# PCB-IEDP.net
KiCad netlist of a schematic drawn in EasyEDA
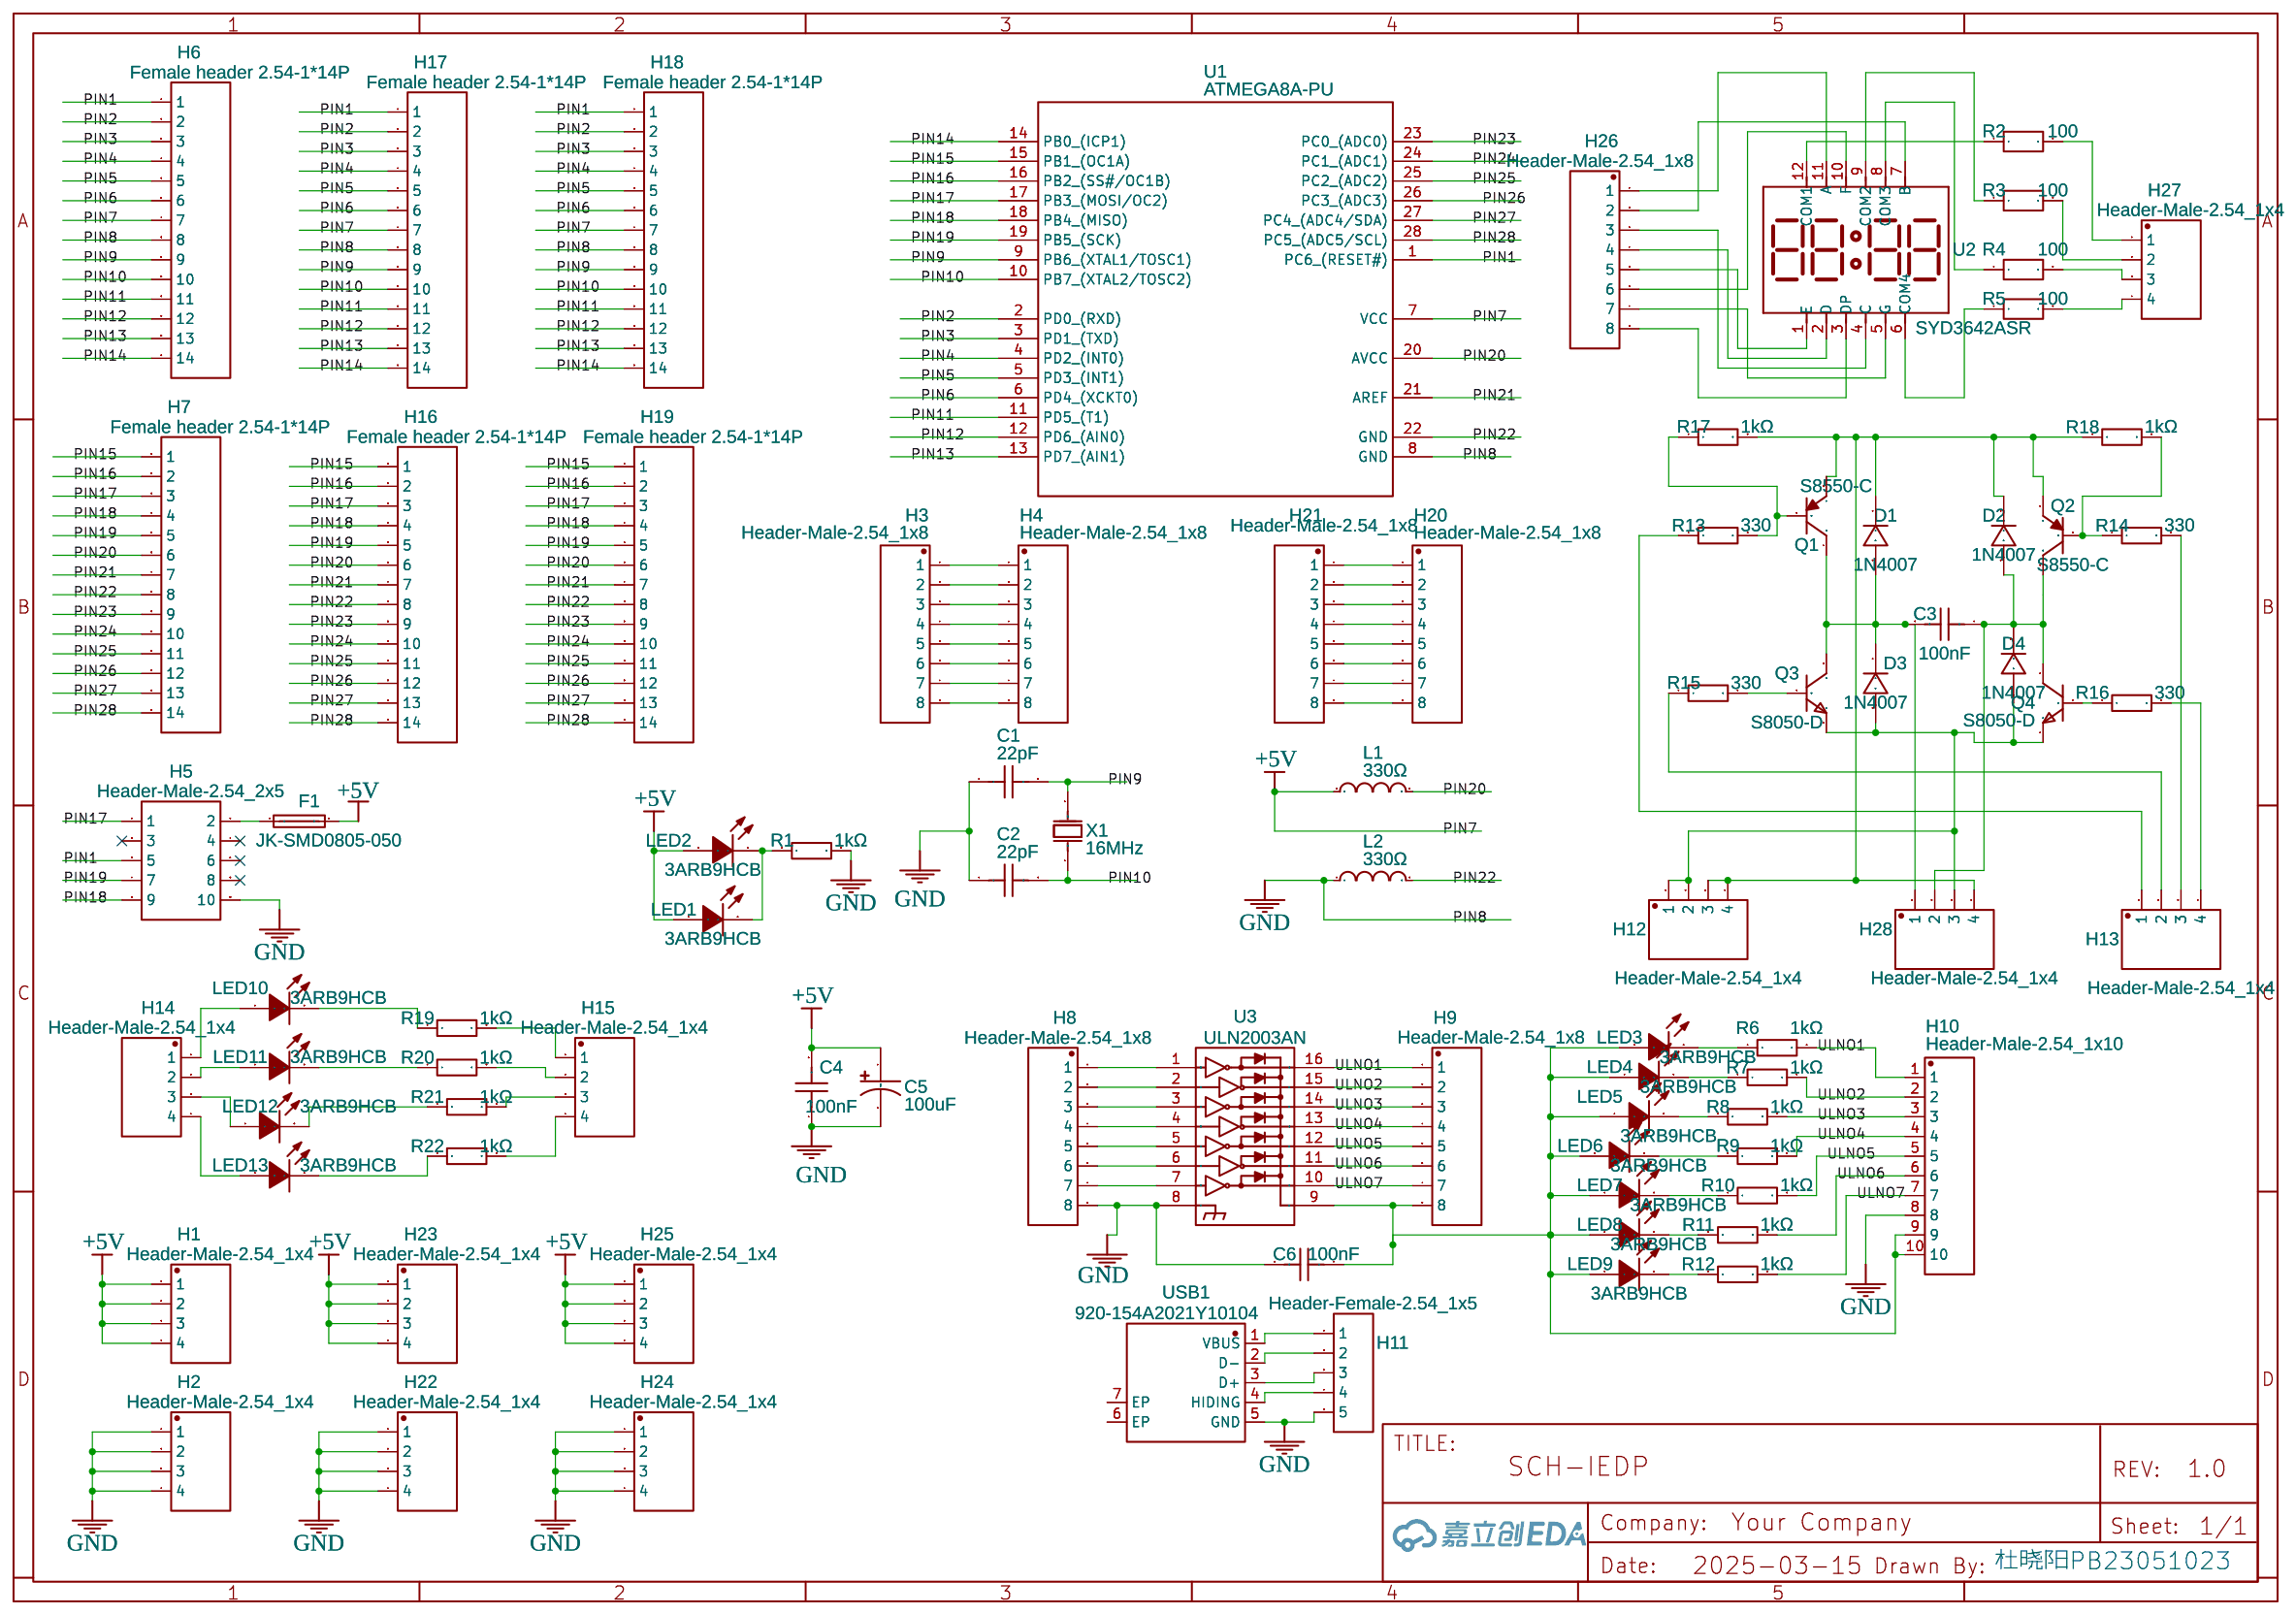
[diagram p0: schematic sheet]

(export (version "E")
  (design (tool "Eeschema 10.0.6"))
  (components
    (comp (ref "C1")
      (value "22pF")
      (fields (field (name "Manufacturer Part") "0805N220J101CT") (field (name "Manufacturer") "Walsin(华新科)"))
      (libsource (lib "") (part "0805N220J101CT"))
    )
    (comp (ref "C2")
      (value "22pF")
      (fields (field (name "Manufacturer Part") "0805N220J101CT") (field (name "Manufacturer") "Walsin(华新科)"))
      (libsource (lib "") (part "0805N220J101CT"))
    )
    (comp (ref "C3")
      (value "100nF")
      (fields (field (name "Manufacturer Part") "ACC-B104K500P52") (field (name "Manufacturer") "FH(风华)"))
      (libsource (lib "") (part "ACC-B104K500P"))
    )
    (comp (ref "C4")
      (value "100nF")
      (fields (field (name "Manufacturer Part") "ACC-B104K500P52") (field (name "Manufacturer") "FH(风华)"))
      (libsource (lib "") (part "ACC-B104K500P_1"))
    )
    (comp (ref "C5")
      (value "100uF")
      (fields
        (field (name "Manufacturer Part") "25YXA100MEFC5X11")
        (field (name "Manufacturer") "rubycon(红宝石)")
      )
      (libsource (lib "") (part "25YXA100MEFC5X11"))
    )
    (comp (ref "C6")
      (value "100nF")
      (fields (field (name "Manufacturer Part") "ACC-B104K500P52") (field (name "Manufacturer") "FH(风华)"))
      (libsource (lib "") (part "ACC-B104K500P"))
    )
    (comp (ref "D1")
      (value "1N4007")
      (fields (field (name "Manufacturer Part") "1N4007A") (field (name "Manufacturer") "LRC(乐山无线电)"))
      (libsource (lib "") (part "1N4007A"))
    )
    (comp (ref "D2")
      (value "1N4007")
      (fields (field (name "Manufacturer Part") "1N4007A") (field (name "Manufacturer") "LRC(乐山无线电)"))
      (libsource (lib "") (part "1N4007A"))
    )
    (comp (ref "D3")
      (value "1N4007")
      (fields (field (name "Manufacturer Part") "1N4007A") (field (name "Manufacturer") "LRC(乐山无线电)"))
      (libsource (lib "") (part "1N4007A"))
    )
    (comp (ref "D4")
      (value "1N4007")
      (fields (field (name "Manufacturer Part") "1N4007A") (field (name "Manufacturer") "LRC(乐山无线电)"))
      (libsource (lib "") (part "1N4007A"))
    )
    (comp (ref "F1")
      (value "JK-SMD0805-050")
      (fields (field (name "Manufacturer") "JK(金科)"))
      (libsource (lib "") (part "JK-SMD0805-050"))
    )
    (comp (ref "H1")
      (value "Header-Male-2.54_1x4")
      (fields (field (name "Manufacturer Part") "B-2100S04P-A110") (field (name "Manufacturer") "Ckmtw(灿科盟)"))
      (libsource (lib "") (part "Header-Male-2.54_1x4"))
    )
    (comp (ref "H2")
      (value "Header-Male-2.54_1x4")
      (fields (field (name "Manufacturer Part") "B-2100S04P-A110") (field (name "Manufacturer") "Ckmtw(灿科盟)"))
      (libsource (lib "") (part "Header-Male-2.54_1x4"))
    )
    (comp (ref "H3")
      (value "Header-Male-2.54_1x8")
      (fields (field (name "Manufacturer Part") "B-2100S08P-A110") (field (name "Manufacturer") "Ckmtw(灿科盟)"))
      (libsource (lib "") (part "Header-Male-2.54_1x8_1"))
    )
    (comp (ref "H4")
      (value "Header-Male-2.54_1x8")
      (fields (field (name "Manufacturer Part") "B-2100S08P-A110") (field (name "Manufacturer") "Ckmtw(灿科盟)"))
      (libsource (lib "") (part "Header-Male-2.54_1x8"))
    )
    (comp (ref "H5")
      (value "Header-Male-2.54_2x5")
      (fields (field (name "Manufacturer Part") "2*5p排针 2.54mm"))
      (libsource (lib "") (part "Header-Male-2.54_2x5"))
    )
    (comp (ref "H6")
      (value "Female header 2.54-1*14P")
      (fields (field (name "Manufacturer Part") "2.54-1*14P母") (field (name "Manufacturer") "BOOMELE(博穆精密)"))
      (libsource (lib "") (part "Female header 2.54-1*14P"))
    )
    (comp (ref "H7")
      (value "Female header 2.54-1*14P")
      (fields (field (name "Manufacturer Part") "2.54-1*14P母") (field (name "Manufacturer") "BOOMELE(博穆精密)"))
      (libsource (lib "") (part "Female header 2.54-1*14P"))
    )
    (comp (ref "H8")
      (value "Header-Male-2.54_1x8")
      (fields (field (name "Manufacturer Part") "B-2100S08P-A110") (field (name "Manufacturer") "Ckmtw(灿科盟)"))
      (libsource (lib "") (part "Header-Male-2.54_1x8_1"))
    )
    (comp (ref "H9")
      (value "Header-Male-2.54_1x8")
      (fields (field (name "Manufacturer Part") "B-2100S08P-A110") (field (name "Manufacturer") "Ckmtw(灿科盟)"))
      (libsource (lib "") (part "Header-Male-2.54_1x8"))
    )
    (comp (ref "H10")
      (value "Header-Male-2.54_1x10")
      (fields (field (name "Manufacturer Part") "2.54-1*10P针") (field (name "Manufacturer") "BOOMELE(博穆精密)"))
      (libsource (lib "") (part "Header-Male-2.54_1x10"))
    )
    (comp (ref "H11")
      (value "Header-Female-2.54_1x5")
      (fields (field (name "Manufacturer Part") "2.54-1*5P母") (field (name "Manufacturer") "BOOMELE(博穆精密)"))
      (libsource (lib "") (part "Header-Female-2.54_1x5"))
    )
    (comp (ref "H12")
      (value "Header-Male-2.54_1x4")
      (fields (field (name "Manufacturer Part") "B-2100S04P-A110") (field (name "Manufacturer") "Ckmtw(灿科盟)"))
      (libsource (lib "") (part "Header-Male-2.54_1x4_2"))
    )
    (comp (ref "H13")
      (value "Header-Male-2.54_1x4")
      (fields (field (name "Manufacturer Part") "B-2100S04P-A110") (field (name "Manufacturer") "Ckmtw(灿科盟)"))
      (libsource (lib "") (part "Header-Male-2.54_1x4_2"))
    )
    (comp (ref "H14")
      (value "Header-Male-2.54_1x4")
      (fields (field (name "Manufacturer Part") "B-2100S04P-A110") (field (name "Manufacturer") "Ckmtw(灿科盟)"))
      (libsource (lib "") (part "Header-Male-2.54_1x4_1"))
    )
    (comp (ref "H15")
      (value "Header-Male-2.54_1x4")
      (fields (field (name "Manufacturer Part") "B-2100S04P-A110") (field (name "Manufacturer") "Ckmtw(灿科盟)"))
      (libsource (lib "") (part "Header-Male-2.54_1x4"))
    )
    (comp (ref "H16")
      (value "Female header 2.54-1*14P")
      (fields (field (name "Manufacturer Part") "2.54-1*14P母") (field (name "Manufacturer") "BOOMELE(博穆精密)"))
      (libsource (lib "") (part "Female header 2.54-1*14P"))
    )
    (comp (ref "H17")
      (value "Female header 2.54-1*14P")
      (fields (field (name "Manufacturer Part") "2.54-1*14P母") (field (name "Manufacturer") "BOOMELE(博穆精密)"))
      (libsource (lib "") (part "Female header 2.54-1*14P"))
    )
    (comp (ref "H18")
      (value "Female header 2.54-1*14P")
      (fields (field (name "Manufacturer Part") "2.54-1*14P母") (field (name "Manufacturer") "BOOMELE(博穆精密)"))
      (libsource (lib "") (part "Female header 2.54-1*14P"))
    )
    (comp (ref "H19")
      (value "Female header 2.54-1*14P")
      (fields (field (name "Manufacturer Part") "2.54-1*14P母") (field (name "Manufacturer") "BOOMELE(博穆精密)"))
      (libsource (lib "") (part "Female header 2.54-1*14P"))
    )
    (comp (ref "H20")
      (value "Header-Male-2.54_1x8")
      (fields (field (name "Manufacturer Part") "B-2100S08P-A110") (field (name "Manufacturer") "Ckmtw(灿科盟)"))
      (libsource (lib "") (part "Header-Male-2.54_1x8"))
    )
    (comp (ref "H21")
      (value "Header-Male-2.54_1x8")
      (fields (field (name "Manufacturer Part") "B-2100S08P-A110") (field (name "Manufacturer") "Ckmtw(灿科盟)"))
      (libsource (lib "") (part "Header-Male-2.54_1x8_1"))
    )
    (comp (ref "H22")
      (value "Header-Male-2.54_1x4")
      (fields (field (name "Manufacturer Part") "B-2100S04P-A110") (field (name "Manufacturer") "Ckmtw(灿科盟)"))
      (libsource (lib "") (part "Header-Male-2.54_1x4"))
    )
    (comp (ref "H23")
      (value "Header-Male-2.54_1x4")
      (fields (field (name "Manufacturer Part") "B-2100S04P-A110") (field (name "Manufacturer") "Ckmtw(灿科盟)"))
      (libsource (lib "") (part "Header-Male-2.54_1x4"))
    )
    (comp (ref "H24")
      (value "Header-Male-2.54_1x4")
      (fields (field (name "Manufacturer Part") "B-2100S04P-A110") (field (name "Manufacturer") "Ckmtw(灿科盟)"))
      (libsource (lib "") (part "Header-Male-2.54_1x4"))
    )
    (comp (ref "H25")
      (value "Header-Male-2.54_1x4")
      (fields (field (name "Manufacturer Part") "B-2100S04P-A110") (field (name "Manufacturer") "Ckmtw(灿科盟)"))
      (libsource (lib "") (part "Header-Male-2.54_1x4"))
    )
    (comp (ref "H26")
      (value "Header-Male-2.54_1x8")
      (fields (field (name "Manufacturer Part") "B-2100S08P-A110") (field (name "Manufacturer") "Ckmtw(灿科盟)"))
      (libsource (lib "") (part "Header-Male-2.54_1x8_1"))
    )
    (comp (ref "H27")
      (value "Header-Male-2.54_1x4")
      (fields (field (name "Manufacturer Part") "B-2100S04P-A110") (field (name "Manufacturer") "Ckmtw(灿科盟)"))
      (libsource (lib "") (part "Header-Male-2.54_1x4"))
    )
    (comp (ref "H28")
      (value "Header-Male-2.54_1x4")
      (fields (field (name "Manufacturer Part") "B-2100S04P-A110") (field (name "Manufacturer") "Ckmtw(灿科盟)"))
      (libsource (lib "") (part "Header-Male-2.54_1x4_2"))
    )
    (comp (ref "L1")
      (value "330Ω")
      (fields (field (name "Manufacturer Part") "CBG201209U301T") (field (name "Manufacturer") "FH(风华)"))
      (libsource (lib "") (part "CBG201209U301T"))
    )
    (comp (ref "L2")
      (value "330Ω")
      (fields (field (name "Manufacturer Part") "CBG201209U301T") (field (name "Manufacturer") "FH(风华)"))
      (libsource (lib "") (part "CBG201209U301T"))
    )
    (comp (ref "LED1") (value "3ARB9HCB") (libsource (lib "") (part "3ARB9HCB")))
    (comp (ref "LED2") (value "3ARB9HCB") (libsource (lib "") (part "3ARB9HCB")))
    (comp (ref "LED3") (value "3ARB9HCB") (libsource (lib "") (part "3ARB9HCB")))
    (comp (ref "LED4") (value "3ARB9HCB") (libsource (lib "") (part "3ARB9HCB")))
    (comp (ref "LED5") (value "3ARB9HCB") (libsource (lib "") (part "3ARB9HCB")))
    (comp (ref "LED6") (value "3ARB9HCB") (libsource (lib "") (part "3ARB9HCB")))
    (comp (ref "LED7") (value "3ARB9HCB") (libsource (lib "") (part "3ARB9HCB")))
    (comp (ref "LED8") (value "3ARB9HCB") (libsource (lib "") (part "3ARB9HCB")))
    (comp (ref "LED9") (value "3ARB9HCB") (libsource (lib "") (part "3ARB9HCB")))
    (comp (ref "LED10") (value "3ARB9HCB") (libsource (lib "") (part "3ARB9HCB")))
    (comp (ref "LED11") (value "3ARB9HCB") (libsource (lib "") (part "3ARB9HCB")))
    (comp (ref "LED12") (value "3ARB9HCB") (libsource (lib "") (part "3ARB9HCB")))
    (comp (ref "LED13") (value "3ARB9HCB") (libsource (lib "") (part "3ARB9HCB")))
    (comp (ref "Q1")
      (value "S8550-C")
      (fields (field (name "Manufacturer") "BLUE ROCKET(蓝箭)"))
      (libsource (lib "") (part "S8550-C"))
    )
    (comp (ref "Q2")
      (value "S8550-C")
      (fields (field (name "Manufacturer") "BLUE ROCKET(蓝箭)"))
      (libsource (lib "") (part "S8550-C_1"))
    )
    (comp (ref "Q3")
      (value "S8050-D")
      (fields (field (name "Manufacturer") "BLUE ROCKET(蓝箭)"))
      (libsource (lib "") (part "S8050-D_1"))
    )
    (comp (ref "Q4")
      (value "S8050-D")
      (fields (field (name "Manufacturer") "BLUE ROCKET(蓝箭)"))
      (libsource (lib "") (part "S8050-D"))
    )
    (comp (ref "R1")
      (value "1kΩ")
      (fields
        (field (name "Manufacturer Part") "TR0805B1K00P0525Z")
        (field (name "Manufacturer") "EVER OHMS(天二科技)")
      )
      (libsource (lib "") (part "TR0805B1KP0525"))
    )
    (comp (ref "R2")
      (value "100")
      (fields (field (name "Manufacturer Part") "Y145313K0000V9L") (field (name "Manufacturer") "VISHAY(威世)"))
      (libsource (lib "") (part "Y145313K0000V9L"))
    )
    (comp (ref "R3")
      (value "100")
      (fields (field (name "Manufacturer Part") "Y145313K0000V9L") (field (name "Manufacturer") "VISHAY(威世)"))
      (libsource (lib "") (part "Y145313K0000V9L"))
    )
    (comp (ref "R4")
      (value "100")
      (fields (field (name "Manufacturer Part") "Y145313K0000V9L") (field (name "Manufacturer") "VISHAY(威世)"))
      (libsource (lib "") (part "Y145313K0000V9L"))
    )
    (comp (ref "R5")
      (value "100")
      (fields (field (name "Manufacturer Part") "Y145313K0000V9L") (field (name "Manufacturer") "VISHAY(威世)"))
      (libsource (lib "") (part "Y145313K0000V9L"))
    )
    (comp (ref "R6")
      (value "1kΩ")
      (fields
        (field (name "Manufacturer Part") "TR0805B1K00P0525Z")
        (field (name "Manufacturer") "EVER OHMS(天二科技)")
      )
      (libsource (lib "") (part "TR0805B1KP0525"))
    )
    (comp (ref "R7")
      (value "1kΩ")
      (fields
        (field (name "Manufacturer Part") "TR0805B1K00P0525Z")
        (field (name "Manufacturer") "EVER OHMS(天二科技)")
      )
      (libsource (lib "") (part "TR0805B1KP0525"))
    )
    (comp (ref "R8")
      (value "1kΩ")
      (fields
        (field (name "Manufacturer Part") "TR0805B1K00P0525Z")
        (field (name "Manufacturer") "EVER OHMS(天二科技)")
      )
      (libsource (lib "") (part "TR0805B1KP0525"))
    )
    (comp (ref "R9")
      (value "1kΩ")
      (fields
        (field (name "Manufacturer Part") "TR0805B1K00P0525Z")
        (field (name "Manufacturer") "EVER OHMS(天二科技)")
      )
      (libsource (lib "") (part "TR0805B1KP0525"))
    )
    (comp (ref "R10")
      (value "1kΩ")
      (fields
        (field (name "Manufacturer Part") "TR0805B1K00P0525Z")
        (field (name "Manufacturer") "EVER OHMS(天二科技)")
      )
      (libsource (lib "") (part "TR0805B1KP0525"))
    )
    (comp (ref "R11")
      (value "1kΩ")
      (fields
        (field (name "Manufacturer Part") "TR0805B1K00P0525Z")
        (field (name "Manufacturer") "EVER OHMS(天二科技)")
      )
      (libsource (lib "") (part "TR0805B1KP0525"))
    )
    (comp (ref "R12")
      (value "1kΩ")
      (fields
        (field (name "Manufacturer Part") "TR0805B1K00P0525Z")
        (field (name "Manufacturer") "EVER OHMS(天二科技)")
      )
      (libsource (lib "") (part "TR0805B1KP0525"))
    )
    (comp (ref "R13")
      (value "330")
      (fields
        (field (name "Manufacturer Part") "TR0805B1K00P0525Z")
        (field (name "Manufacturer") "EVER OHMS(天二科技)")
      )
      (libsource (lib "") (part "TR0805B1KP0525"))
    )
    (comp (ref "R14")
      (value "330")
      (fields
        (field (name "Manufacturer Part") "TR0805B1K00P0525Z")
        (field (name "Manufacturer") "EVER OHMS(天二科技)")
      )
      (libsource (lib "") (part "TR0805B1KP0525"))
    )
    (comp (ref "R15")
      (value "330")
      (fields
        (field (name "Manufacturer Part") "TR0805B1K00P0525Z")
        (field (name "Manufacturer") "EVER OHMS(天二科技)")
      )
      (libsource (lib "") (part "TR0805B1KP0525"))
    )
    (comp (ref "R16")
      (value "330")
      (fields
        (field (name "Manufacturer Part") "TR0805B1K00P0525Z")
        (field (name "Manufacturer") "EVER OHMS(天二科技)")
      )
      (libsource (lib "") (part "TR0805B1KP0525"))
    )
    (comp (ref "R17")
      (value "1kΩ")
      (fields
        (field (name "Manufacturer Part") "TR0805B1K00P0525Z")
        (field (name "Manufacturer") "EVER OHMS(天二科技)")
      )
      (libsource (lib "") (part "TR0805B1KP0525"))
    )
    (comp (ref "R18")
      (value "1kΩ")
      (fields
        (field (name "Manufacturer Part") "TR0805B1K00P0525Z")
        (field (name "Manufacturer") "EVER OHMS(天二科技)")
      )
      (libsource (lib "") (part "TR0805B1KP0525"))
    )
    (comp (ref "R19")
      (value "1kΩ")
      (fields
        (field (name "Manufacturer Part") "TR0805B1K00P0525Z")
        (field (name "Manufacturer") "EVER OHMS(天二科技)")
      )
      (libsource (lib "") (part "TR0805B1KP0525"))
    )
    (comp (ref "R20")
      (value "1kΩ")
      (fields
        (field (name "Manufacturer Part") "TR0805B1K00P0525Z")
        (field (name "Manufacturer") "EVER OHMS(天二科技)")
      )
      (libsource (lib "") (part "TR0805B1KP0525"))
    )
    (comp (ref "R21")
      (value "1kΩ")
      (fields
        (field (name "Manufacturer Part") "TR0805B1K00P0525Z")
        (field (name "Manufacturer") "EVER OHMS(天二科技)")
      )
      (libsource (lib "") (part "TR0805B1KP0525"))
    )
    (comp (ref "R22")
      (value "1kΩ")
      (fields
        (field (name "Manufacturer Part") "TR0805B1K00P0525Z")
        (field (name "Manufacturer") "EVER OHMS(天二科技)")
      )
      (libsource (lib "") (part "TR0805B1KP0525"))
    )
    (comp (ref "U1")
      (value "ATMEGA8A-PU")
      (fields (field (name "Manufacturer") "MICROCHIP(美国微芯)"))
      (libsource (lib "") (part "ATMEGA8A-PU"))
    )
    (comp (ref "U2") (value "SYD3642ASR") (libsource (lib "") (part "SYD3642ASR")))
    (comp (ref "U3")
      (value "ULN2003AN")
      (fields (field (name "Manufacturer") "TI(德州仪器)"))
      (libsource (lib "") (part "ULN2003AN"))
    )
    (comp (ref "USB1")
      (value "920-154A2021Y10104")
      (fields (field (name "Manufacturer") "精拓金"))
      (libsource (lib "") (part "920-154A2021Y10104"))
    )
    (comp (ref "X1")
      (value "16MHz")
      (fields (field (name "Manufacturer Part") "X49SD16MSD2SC") (field (name "Manufacturer") "YXC(扬兴晶振)"))
      (libsource (lib "") (part "X49SD16MSD2SC"))
    )
  )
  (nets
    (net (code "1") (name "+5V") (class "Default")
      (node (ref "C4") (pin "2") (pinfunction "2_2") (pintype "unspecified"))
      (node (ref "C5") (pin "1") (pinfunction "1_1") (pintype "unspecified"))
      (node (ref "F1") (pin "2") (pinfunction "2_2") (pintype "unspecified"))
      (node (ref "H1") (pin "1") (pinfunction "1_1") (pintype "unspecified"))
      (node (ref "H1") (pin "2") (pinfunction "2_2") (pintype "unspecified"))
      (node (ref "H1") (pin "3") (pinfunction "3_3") (pintype "unspecified"))
      (node (ref "H1") (pin "4") (pinfunction "4_4") (pintype "unspecified"))
      (node (ref "H17") (pin "7") (pinfunction "7_7") (pintype "input"))
      (node (ref "H18") (pin "7") (pinfunction "7_7") (pintype "input"))
      (node (ref "H23") (pin "1") (pinfunction "1_1") (pintype "unspecified"))
      (node (ref "H23") (pin "2") (pinfunction "2_2") (pintype "unspecified"))
      (node (ref "H23") (pin "3") (pinfunction "3_3") (pintype "unspecified"))
      (node (ref "H23") (pin "4") (pinfunction "4_4") (pintype "unspecified"))
      (node (ref "H25") (pin "1") (pinfunction "1_1") (pintype "unspecified"))
      (node (ref "H25") (pin "2") (pinfunction "2_2") (pintype "unspecified"))
      (node (ref "H25") (pin "3") (pinfunction "3_3") (pintype "unspecified"))
      (node (ref "H25") (pin "4") (pinfunction "4_4") (pintype "unspecified"))
      (node (ref "H6") (pin "7") (pinfunction "7_7") (pintype "input"))
      (node (ref "L1") (pin "1") (pinfunction "1_1") (pintype "unspecified"))
      (node (ref "LED1") (pin "1") (pinfunction "A_1") (pintype "unspecified"))
      (node (ref "LED2") (pin "1") (pinfunction "A_1") (pintype "unspecified"))
      (node (ref "U1") (pin "7") (pinfunction "VCC_7") (pintype "passive"))
    )
    (net (code "2") (name "/PIN1") (class "Default")
      (node (ref "H17") (pin "1") (pinfunction "1_1") (pintype "input"))
      (node (ref "H18") (pin "1") (pinfunction "1_1") (pintype "input"))
      (node (ref "H5") (pin "5") (pinfunction "5_5") (pintype "input"))
      (node (ref "H6") (pin "1") (pinfunction "1_1") (pintype "input"))
      (node (ref "U1") (pin "1") (pinfunction "PC6_(RESET#)_1") (pintype "bidirectional"))
    )
    (net (code "3") (name "/PIN2") (class "Default")
      (node (ref "H17") (pin "2") (pinfunction "2_2") (pintype "input"))
      (node (ref "H18") (pin "2") (pinfunction "2_2") (pintype "input"))
      (node (ref "H6") (pin "2") (pinfunction "2_2") (pintype "input"))
      (node (ref "U1") (pin "2") (pinfunction "PD0_(RXD)_2") (pintype "bidirectional"))
    )
    (net (code "4") (name "/PIN3") (class "Default")
      (node (ref "H17") (pin "3") (pinfunction "3_3") (pintype "input"))
      (node (ref "H18") (pin "3") (pinfunction "3_3") (pintype "input"))
      (node (ref "H6") (pin "3") (pinfunction "3_3") (pintype "input"))
      (node (ref "U1") (pin "3") (pinfunction "PD1_(TXD)_3") (pintype "bidirectional"))
    )
    (net (code "5") (name "/PIN4") (class "Default")
      (node (ref "H17") (pin "4") (pinfunction "4_4") (pintype "input"))
      (node (ref "H18") (pin "4") (pinfunction "4_4") (pintype "input"))
      (node (ref "H6") (pin "4") (pinfunction "4_4") (pintype "input"))
      (node (ref "U1") (pin "4") (pinfunction "PD2_(INT0)_4") (pintype "bidirectional"))
    )
    (net (code "6") (name "/PIN5") (class "Default")
      (node (ref "H17") (pin "5") (pinfunction "5_5") (pintype "input"))
      (node (ref "H18") (pin "5") (pinfunction "5_5") (pintype "input"))
      (node (ref "H6") (pin "5") (pinfunction "5_5") (pintype "input"))
      (node (ref "U1") (pin "5") (pinfunction "PD3_(INT1)_5") (pintype "bidirectional"))
    )
    (net (code "7") (name "/PIN6") (class "Default")
      (node (ref "H17") (pin "6") (pinfunction "6_6") (pintype "input"))
      (node (ref "H18") (pin "6") (pinfunction "6_6") (pintype "input"))
      (node (ref "H6") (pin "6") (pinfunction "6_6") (pintype "input"))
      (node (ref "U1") (pin "6") (pinfunction "PD4_(XCKT0)_6") (pintype "bidirectional"))
    )
    (net (code "8") (name "/PIN9") (class "Default")
      (node (ref "C1") (pin "2") (pinfunction "2_2") (pintype "unspecified"))
      (node (ref "H17") (pin "9") (pinfunction "9_9") (pintype "input"))
      (node (ref "H18") (pin "9") (pinfunction "9_9") (pintype "input"))
      (node (ref "H6") (pin "9") (pinfunction "9_9") (pintype "input"))
      (node (ref "U1") (pin "9") (pinfunction "PB6_(XTAL1/TOSC1)_9") (pintype "bidirectional"))
      (node (ref "X1") (pin "2") (pinfunction "OSC2_2") (pintype "input"))
    )
    (net (code "9") (name "/PIN10") (class "Default")
      (node (ref "C2") (pin "2") (pinfunction "2_2") (pintype "unspecified"))
      (node (ref "H17") (pin "10") (pinfunction "10_10") (pintype "input"))
      (node (ref "H18") (pin "10") (pinfunction "10_10") (pintype "input"))
      (node (ref "H6") (pin "10") (pinfunction "10_10") (pintype "input"))
      (node (ref "U1") (pin "10") (pinfunction "PB7_(XTAL2/TOSC2)_10") (pintype "bidirectional"))
      (node (ref "X1") (pin "1") (pinfunction "OSC1_1") (pintype "input"))
    )
    (net (code "10") (name "/PIN11") (class "Default")
      (node (ref "H17") (pin "11") (pinfunction "11_11") (pintype "input"))
      (node (ref "H18") (pin "11") (pinfunction "11_11") (pintype "input"))
      (node (ref "H6") (pin "11") (pinfunction "11_11") (pintype "input"))
      (node (ref "U1") (pin "11") (pinfunction "PD5_(T1)_11") (pintype "bidirectional"))
    )
    (net (code "11") (name "/PIN12") (class "Default")
      (node (ref "H17") (pin "12") (pinfunction "12_12") (pintype "input"))
      (node (ref "H18") (pin "12") (pinfunction "12_12") (pintype "input"))
      (node (ref "H6") (pin "12") (pinfunction "12_12") (pintype "input"))
      (node (ref "U1") (pin "12") (pinfunction "PD6_(AIN0)_12") (pintype "bidirectional"))
    )
    (net (code "12") (name "/PIN13") (class "Default")
      (node (ref "H17") (pin "13") (pinfunction "13_13") (pintype "input"))
      (node (ref "H18") (pin "13") (pinfunction "13_13") (pintype "input"))
      (node (ref "H6") (pin "13") (pinfunction "13_13") (pintype "input"))
      (node (ref "U1") (pin "13") (pinfunction "PD7_(AIN1)_13") (pintype "bidirectional"))
    )
    (net (code "13") (name "/PIN14") (class "Default")
      (node (ref "H17") (pin "14") (pinfunction "14_14") (pintype "input"))
      (node (ref "H18") (pin "14") (pinfunction "14_14") (pintype "input"))
      (node (ref "H6") (pin "14") (pinfunction "14_14") (pintype "input"))
      (node (ref "U1") (pin "14") (pinfunction "PB0_(ICP1)_14") (pintype "bidirectional"))
    )
    (net (code "14") (name "/PIN15") (class "Default")
      (node (ref "H16") (pin "1") (pinfunction "1_1") (pintype "input"))
      (node (ref "H19") (pin "1") (pinfunction "1_1") (pintype "input"))
      (node (ref "H7") (pin "1") (pinfunction "1_1") (pintype "input"))
      (node (ref "U1") (pin "15") (pinfunction "PB1_(OC1A)_15") (pintype "bidirectional"))
    )
    (net (code "15") (name "/PIN16") (class "Default")
      (node (ref "H16") (pin "2") (pinfunction "2_2") (pintype "input"))
      (node (ref "H19") (pin "2") (pinfunction "2_2") (pintype "input"))
      (node (ref "H7") (pin "2") (pinfunction "2_2") (pintype "input"))
      (node (ref "U1") (pin "16") (pinfunction "PB2_(SS#/OC1B)_16") (pintype "bidirectional"))
    )
    (net (code "16") (name "/PIN17") (class "Default")
      (node (ref "H16") (pin "3") (pinfunction "3_3") (pintype "input"))
      (node (ref "H19") (pin "3") (pinfunction "3_3") (pintype "input"))
      (node (ref "H5") (pin "1") (pinfunction "1_1") (pintype "input"))
      (node (ref "H7") (pin "3") (pinfunction "3_3") (pintype "input"))
      (node (ref "U1") (pin "17") (pinfunction "PB3_(MOSI/OC2)_17") (pintype "bidirectional"))
    )
    (net (code "17") (name "/PIN18") (class "Default")
      (node (ref "H16") (pin "4") (pinfunction "4_4") (pintype "input"))
      (node (ref "H19") (pin "4") (pinfunction "4_4") (pintype "input"))
      (node (ref "H5") (pin "9") (pinfunction "9_9") (pintype "input"))
      (node (ref "H7") (pin "4") (pinfunction "4_4") (pintype "input"))
      (node (ref "U1") (pin "18") (pinfunction "PB4_(MISO)_18") (pintype "bidirectional"))
    )
    (net (code "18") (name "/PIN19") (class "Default")
      (node (ref "H16") (pin "5") (pinfunction "5_5") (pintype "input"))
      (node (ref "H19") (pin "5") (pinfunction "5_5") (pintype "input"))
      (node (ref "H5") (pin "7") (pinfunction "7_7") (pintype "input"))
      (node (ref "H7") (pin "5") (pinfunction "5_5") (pintype "input"))
      (node (ref "U1") (pin "19") (pinfunction "PB5_(SCK)_19") (pintype "bidirectional"))
    )
    (net (code "19") (name "/PIN20") (class "Default")
      (node (ref "H16") (pin "6") (pinfunction "6_6") (pintype "input"))
      (node (ref "H19") (pin "6") (pinfunction "6_6") (pintype "input"))
      (node (ref "H7") (pin "6") (pinfunction "6_6") (pintype "input"))
      (node (ref "L1") (pin "2") (pinfunction "2_2") (pintype "unspecified"))
      (node (ref "U1") (pin "20") (pinfunction "AVCC_20") (pintype "passive"))
    )
    (net (code "20") (name "/PIN21") (class "Default")
      (node (ref "H16") (pin "7") (pinfunction "7_7") (pintype "input"))
      (node (ref "H19") (pin "7") (pinfunction "7_7") (pintype "input"))
      (node (ref "H7") (pin "7") (pinfunction "7_7") (pintype "input"))
      (node (ref "U1") (pin "21") (pinfunction "AREF_21") (pintype "unspecified"))
    )
    (net (code "21") (name "/PIN22") (class "Default")
      (node (ref "H16") (pin "8") (pinfunction "8_8") (pintype "input"))
      (node (ref "H19") (pin "8") (pinfunction "8_8") (pintype "input"))
      (node (ref "H7") (pin "8") (pinfunction "8_8") (pintype "input"))
      (node (ref "L2") (pin "2") (pinfunction "2_2") (pintype "unspecified"))
      (node (ref "U1") (pin "22") (pinfunction "GND_22") (pintype "passive"))
    )
    (net (code "22") (name "/PIN23") (class "Default")
      (node (ref "H16") (pin "9") (pinfunction "9_9") (pintype "input"))
      (node (ref "H19") (pin "9") (pinfunction "9_9") (pintype "input"))
      (node (ref "H7") (pin "9") (pinfunction "9_9") (pintype "input"))
      (node (ref "U1") (pin "23") (pinfunction "PC0_(ADC0)_23") (pintype "bidirectional"))
    )
    (net (code "23") (name "/PIN24") (class "Default")
      (node (ref "H16") (pin "10") (pinfunction "10_10") (pintype "input"))
      (node (ref "H19") (pin "10") (pinfunction "10_10") (pintype "input"))
      (node (ref "H7") (pin "10") (pinfunction "10_10") (pintype "input"))
      (node (ref "U1") (pin "24") (pinfunction "PC1_(ADC1)_24") (pintype "bidirectional"))
    )
    (net (code "24") (name "/PIN25") (class "Default")
      (node (ref "H16") (pin "11") (pinfunction "11_11") (pintype "input"))
      (node (ref "H19") (pin "11") (pinfunction "11_11") (pintype "input"))
      (node (ref "H7") (pin "11") (pinfunction "11_11") (pintype "input"))
      (node (ref "U1") (pin "25") (pinfunction "PC2_(ADC2)_25") (pintype "bidirectional"))
    )
    (net (code "25") (name "/PIN26") (class "Default")
      (node (ref "H16") (pin "12") (pinfunction "12_12") (pintype "input"))
      (node (ref "H19") (pin "12") (pinfunction "12_12") (pintype "input"))
      (node (ref "H7") (pin "12") (pinfunction "12_12") (pintype "input"))
      (node (ref "U1") (pin "26") (pinfunction "PC3_(ADC3)_26") (pintype "bidirectional"))
    )
    (net (code "26") (name "/PIN27") (class "Default")
      (node (ref "H16") (pin "13") (pinfunction "13_13") (pintype "input"))
      (node (ref "H19") (pin "13") (pinfunction "13_13") (pintype "input"))
      (node (ref "H7") (pin "13") (pinfunction "13_13") (pintype "input"))
      (node (ref "U1") (pin "27") (pinfunction "PC4_(ADC4/SDA)_27") (pintype "bidirectional"))
    )
    (net (code "27") (name "/PIN28") (class "Default")
      (node (ref "H16") (pin "14") (pinfunction "14_14") (pintype "input"))
      (node (ref "H19") (pin "14") (pinfunction "14_14") (pintype "input"))
      (node (ref "H7") (pin "14") (pinfunction "14_14") (pintype "input"))
      (node (ref "U1") (pin "28") (pinfunction "PC5_(ADC5/SCL)_28") (pintype "bidirectional"))
    )
    (net (code "28") (name "/ULNO1") (class "Default")
      (node (ref "H10") (pin "1") (pinfunction "1_1") (pintype "unspecified"))
      (node (ref "H9") (pin "1") (pinfunction "1_1") (pintype "unspecified"))
      (node (ref "R6") (pin "2") (pinfunction "2_2") (pintype "unspecified"))
      (node (ref "U3") (pin "16") (pinfunction "1C_16") (pintype "unspecified"))
    )
    (net (code "29") (name "/ULNO2") (class "Default")
      (node (ref "H10") (pin "2") (pinfunction "2_2") (pintype "unspecified"))
      (node (ref "H9") (pin "2") (pinfunction "2_2") (pintype "unspecified"))
      (node (ref "R7") (pin "2") (pinfunction "2_2") (pintype "unspecified"))
      (node (ref "U3") (pin "15") (pinfunction "2C_15") (pintype "unspecified"))
    )
    (net (code "30") (name "/ULNO3") (class "Default")
      (node (ref "H10") (pin "3") (pinfunction "3_3") (pintype "unspecified"))
      (node (ref "H9") (pin "3") (pinfunction "3_3") (pintype "unspecified"))
      (node (ref "R8") (pin "2") (pinfunction "2_2") (pintype "unspecified"))
      (node (ref "U3") (pin "14") (pinfunction "3C_14") (pintype "unspecified"))
    )
    (net (code "31") (name "/ULNO4") (class "Default")
      (node (ref "H10") (pin "4") (pinfunction "4_4") (pintype "unspecified"))
      (node (ref "H9") (pin "4") (pinfunction "4_4") (pintype "unspecified"))
      (node (ref "R9") (pin "2") (pinfunction "2_2") (pintype "unspecified"))
      (node (ref "U3") (pin "13") (pinfunction "4C_13") (pintype "unspecified"))
    )
    (net (code "32") (name "/ULNO5") (class "Default")
      (node (ref "H10") (pin "5") (pinfunction "5_5") (pintype "unspecified"))
      (node (ref "H9") (pin "5") (pinfunction "5_5") (pintype "unspecified"))
      (node (ref "R10") (pin "2") (pinfunction "2_2") (pintype "unspecified"))
      (node (ref "U3") (pin "12") (pinfunction "5C_12") (pintype "unspecified"))
    )
    (net (code "33") (name "/ULNO6") (class "Default")
      (node (ref "H10") (pin "6") (pinfunction "6_6") (pintype "unspecified"))
      (node (ref "H9") (pin "6") (pinfunction "6_6") (pintype "unspecified"))
      (node (ref "R11") (pin "2") (pinfunction "2_2") (pintype "unspecified"))
      (node (ref "U3") (pin "11") (pinfunction "6C_11") (pintype "unspecified"))
    )
    (net (code "34") (name "/ULNO7") (class "Default")
      (node (ref "H10") (pin "7") (pinfunction "7_7") (pintype "unspecified"))
      (node (ref "H9") (pin "7") (pinfunction "7_7") (pintype "unspecified"))
      (node (ref "R12") (pin "2") (pinfunction "2_2") (pintype "unspecified"))
      (node (ref "U3") (pin "10") (pinfunction "7C_10") (pintype "unspecified"))
    )
    (net (code "35") (name "GND") (class "Default")
      (node (ref "C1") (pin "1") (pinfunction "1_1") (pintype "unspecified"))
      (node (ref "C2") (pin "1") (pinfunction "1_1") (pintype "unspecified"))
      (node (ref "C4") (pin "1") (pinfunction "1_1") (pintype "unspecified"))
      (node (ref "C5") (pin "2") (pinfunction "2_2") (pintype "unspecified"))
      (node (ref "C6") (pin "2") (pinfunction "2_2") (pintype "unspecified"))
      (node (ref "H10") (pin "8") (pinfunction "8_8") (pintype "unspecified"))
      (node (ref "H11") (pin "5") (pinfunction "5_5") (pintype "input"))
      (node (ref "H17") (pin "8") (pinfunction "8_8") (pintype "input"))
      (node (ref "H18") (pin "8") (pinfunction "8_8") (pintype "input"))
      (node (ref "H2") (pin "1") (pinfunction "1_1") (pintype "unspecified"))
      (node (ref "H2") (pin "2") (pinfunction "2_2") (pintype "unspecified"))
      (node (ref "H2") (pin "3") (pinfunction "3_3") (pintype "unspecified"))
      (node (ref "H2") (pin "4") (pinfunction "4_4") (pintype "unspecified"))
      (node (ref "H22") (pin "1") (pinfunction "1_1") (pintype "unspecified"))
      (node (ref "H22") (pin "2") (pinfunction "2_2") (pintype "unspecified"))
      (node (ref "H22") (pin "3") (pinfunction "3_3") (pintype "unspecified"))
      (node (ref "H22") (pin "4") (pinfunction "4_4") (pintype "unspecified"))
      (node (ref "H24") (pin "1") (pinfunction "1_1") (pintype "unspecified"))
      (node (ref "H24") (pin "2") (pinfunction "2_2") (pintype "unspecified"))
      (node (ref "H24") (pin "3") (pinfunction "3_3") (pintype "unspecified"))
      (node (ref "H24") (pin "4") (pinfunction "4_4") (pintype "unspecified"))
      (node (ref "H5") (pin "10") (pinfunction "10_10") (pintype "input"))
      (node (ref "H6") (pin "8") (pinfunction "8_8") (pintype "input"))
      (node (ref "H8") (pin "8") (pinfunction "8_8") (pintype "unspecified"))
      (node (ref "L2") (pin "1") (pinfunction "1_1") (pintype "unspecified"))
      (node (ref "R1") (pin "2") (pinfunction "2_2") (pintype "unspecified"))
      (node (ref "U1") (pin "8") (pinfunction "GND_8") (pintype "passive"))
      (node (ref "U3") (pin "8") (pinfunction "E_8") (pintype "unspecified"))
      (node (ref "USB1") (pin "5") (pinfunction "GND_5") (pintype "unspecified"))
    )
    (net (code "36") (name "Net-(F1-Pad1)") (class "Default")
      (node (ref "F1") (pin "1") (pinfunction "1_1") (pintype "unspecified"))
      (node (ref "H5") (pin "2") (pinfunction "2_2") (pintype "input"))
    )
    (net (code "37") (name "Net-(H3-Pad1)") (class "Default")
      (node (ref "H3") (pin "1") (pinfunction "1_1") (pintype "unspecified"))
      (node (ref "H4") (pin "1") (pinfunction "1_1") (pintype "unspecified"))
    )
    (net (code "38") (name "Net-(H3-Pad2)") (class "Default")
      (node (ref "H3") (pin "2") (pinfunction "2_2") (pintype "unspecified"))
      (node (ref "H4") (pin "2") (pinfunction "2_2") (pintype "unspecified"))
    )
    (net (code "39") (name "Net-(H3-Pad3)") (class "Default")
      (node (ref "H3") (pin "3") (pinfunction "3_3") (pintype "unspecified"))
      (node (ref "H4") (pin "3") (pinfunction "3_3") (pintype "unspecified"))
    )
    (net (code "40") (name "Net-(H3-Pad4)") (class "Default")
      (node (ref "H3") (pin "4") (pinfunction "4_4") (pintype "unspecified"))
      (node (ref "H4") (pin "4") (pinfunction "4_4") (pintype "unspecified"))
    )
    (net (code "41") (name "Net-(H3-Pad5)") (class "Default")
      (node (ref "H3") (pin "5") (pinfunction "5_5") (pintype "unspecified"))
      (node (ref "H4") (pin "5") (pinfunction "5_5") (pintype "unspecified"))
    )
    (net (code "42") (name "Net-(H3-Pad6)") (class "Default")
      (node (ref "H3") (pin "6") (pinfunction "6_6") (pintype "unspecified"))
      (node (ref "H4") (pin "6") (pinfunction "6_6") (pintype "unspecified"))
    )
    (net (code "43") (name "Net-(H3-Pad7)") (class "Default")
      (node (ref "H3") (pin "7") (pinfunction "7_7") (pintype "unspecified"))
      (node (ref "H4") (pin "7") (pinfunction "7_7") (pintype "unspecified"))
    )
    (net (code "44") (name "Net-(H3-Pad8)") (class "Default")
      (node (ref "H3") (pin "8") (pinfunction "8_8") (pintype "unspecified"))
      (node (ref "H4") (pin "8") (pinfunction "8_8") (pintype "unspecified"))
    )
    (net (code "45") (name "Net-(H13-Pad1)") (class "Default")
      (node (ref "H13") (pin "1") (pinfunction "1_1") (pintype "unspecified"))
      (node (ref "R13") (pin "1") (pinfunction "1_1") (pintype "unspecified"))
    )
    (net (code "46") (name "Net-(H13-Pad2)") (class "Default")
      (node (ref "H13") (pin "2") (pinfunction "2_2") (pintype "unspecified"))
      (node (ref "R15") (pin "1") (pinfunction "1_1") (pintype "unspecified"))
    )
    (net (code "47") (name "Net-(H13-Pad3)") (class "Default")
      (node (ref "H13") (pin "3") (pinfunction "3_3") (pintype "unspecified"))
      (node (ref "R14") (pin "2") (pinfunction "2_2") (pintype "unspecified"))
    )
    (net (code "48") (name "Net-(H13-Pad4)") (class "Default")
      (node (ref "H13") (pin "4") (pinfunction "4_4") (pintype "unspecified"))
      (node (ref "R16") (pin "2") (pinfunction "2_2") (pintype "unspecified"))
    )
    (net (code "49") (name "Net-(H15-Pad1)") (class "Default")
      (node (ref "H15") (pin "1") (pinfunction "1_1") (pintype "unspecified"))
      (node (ref "R19") (pin "2") (pinfunction "2_2") (pintype "unspecified"))
    )
    (net (code "50") (name "Net-(H15-Pad2)") (class "Default")
      (node (ref "H15") (pin "2") (pinfunction "2_2") (pintype "unspecified"))
      (node (ref "R20") (pin "2") (pinfunction "2_2") (pintype "unspecified"))
    )
    (net (code "51") (name "Net-(H15-Pad3)") (class "Default")
      (node (ref "H15") (pin "3") (pinfunction "3_3") (pintype "unspecified"))
      (node (ref "R21") (pin "2") (pinfunction "2_2") (pintype "unspecified"))
    )
    (net (code "52") (name "Net-(H15-Pad4)") (class "Default")
      (node (ref "H15") (pin "4") (pinfunction "4_4") (pintype "unspecified"))
      (node (ref "R22") (pin "2") (pinfunction "2_2") (pintype "unspecified"))
    )
    (net (code "53") (name "Net-(H20-Pad1)") (class "Default")
      (node (ref "H20") (pin "1") (pinfunction "1_1") (pintype "unspecified"))
      (node (ref "H21") (pin "1") (pinfunction "1_1") (pintype "unspecified"))
    )
    (net (code "54") (name "Net-(H20-Pad2)") (class "Default")
      (node (ref "H20") (pin "2") (pinfunction "2_2") (pintype "unspecified"))
      (node (ref "H21") (pin "2") (pinfunction "2_2") (pintype "unspecified"))
    )
    (net (code "55") (name "Net-(H20-Pad3)") (class "Default")
      (node (ref "H20") (pin "3") (pinfunction "3_3") (pintype "unspecified"))
      (node (ref "H21") (pin "3") (pinfunction "3_3") (pintype "unspecified"))
    )
    (net (code "56") (name "Net-(H20-Pad4)") (class "Default")
      (node (ref "H20") (pin "4") (pinfunction "4_4") (pintype "unspecified"))
      (node (ref "H21") (pin "4") (pinfunction "4_4") (pintype "unspecified"))
    )
    (net (code "57") (name "Net-(H20-Pad5)") (class "Default")
      (node (ref "H20") (pin "5") (pinfunction "5_5") (pintype "unspecified"))
      (node (ref "H21") (pin "5") (pinfunction "5_5") (pintype "unspecified"))
    )
    (net (code "58") (name "Net-(H20-Pad6)") (class "Default")
      (node (ref "H20") (pin "6") (pinfunction "6_6") (pintype "unspecified"))
      (node (ref "H21") (pin "6") (pinfunction "6_6") (pintype "unspecified"))
    )
    (net (code "59") (name "Net-(H20-Pad7)") (class "Default")
      (node (ref "H20") (pin "7") (pinfunction "7_7") (pintype "unspecified"))
      (node (ref "H21") (pin "7") (pinfunction "7_7") (pintype "unspecified"))
    )
    (net (code "60") (name "Net-(H20-Pad8)") (class "Default")
      (node (ref "H20") (pin "8") (pinfunction "8_8") (pintype "unspecified"))
      (node (ref "H21") (pin "8") (pinfunction "8_8") (pintype "unspecified"))
    )
    (net (code "61") (name "Net-(H27-Pad1)") (class "Default")
      (node (ref "H27") (pin "1") (pinfunction "1_1") (pintype "unspecified"))
      (node (ref "R2") (pin "2") (pinfunction "2_2") (pintype "unspecified"))
    )
    (net (code "62") (name "Net-(H27-Pad2)") (class "Default")
      (node (ref "H27") (pin "2") (pinfunction "2_2") (pintype "unspecified"))
      (node (ref "R3") (pin "2") (pinfunction "2_2") (pintype "unspecified"))
    )
    (net (code "63") (name "Net-(H27-Pad3)") (class "Default")
      (node (ref "H27") (pin "3") (pinfunction "3_3") (pintype "unspecified"))
      (node (ref "R4") (pin "2") (pinfunction "2_2") (pintype "unspecified"))
    )
    (net (code "64") (name "Net-(H27-Pad4)") (class "Default")
      (node (ref "H27") (pin "4") (pinfunction "4_4") (pintype "unspecified"))
      (node (ref "R5") (pin "2") (pinfunction "2_2") (pintype "unspecified"))
    )
    (net (code "65") (name "Net-(LED1-K)") (class "Default")
      (node (ref "LED1") (pin "2") (pinfunction "K_2") (pintype "unspecified"))
      (node (ref "LED2") (pin "2") (pinfunction "K_2") (pintype "unspecified"))
      (node (ref "R1") (pin "1") (pinfunction "1_1") (pintype "unspecified"))
    )
    (net (code "66") (name "Net-(LED3-A)") (class "Default")
      (node (ref "C6") (pin "1") (pinfunction "1_1") (pintype "unspecified"))
      (node (ref "H10") (pin "10") (pinfunction "10_10") (pintype "unspecified"))
      (node (ref "H10") (pin "9") (pinfunction "9_9") (pintype "unspecified"))
      (node (ref "H9") (pin "8") (pinfunction "8_8") (pintype "unspecified"))
      (node (ref "LED3") (pin "1") (pinfunction "A_1") (pintype "unspecified"))
      (node (ref "LED4") (pin "1") (pinfunction "A_1") (pintype "unspecified"))
      (node (ref "LED5") (pin "1") (pinfunction "A_1") (pintype "unspecified"))
      (node (ref "LED6") (pin "1") (pinfunction "A_1") (pintype "unspecified"))
      (node (ref "LED7") (pin "1") (pinfunction "A_1") (pintype "unspecified"))
      (node (ref "LED8") (pin "1") (pinfunction "A_1") (pintype "unspecified"))
      (node (ref "LED9") (pin "1") (pinfunction "A_1") (pintype "unspecified"))
      (node (ref "U3") (pin "9") (pinfunction "COM_9") (pintype "unspecified"))
    )
    (net (code "67") (name "Net-(LED3-K)") (class "Default")
      (node (ref "LED3") (pin "2") (pinfunction "K_2") (pintype "unspecified"))
      (node (ref "R6") (pin "1") (pinfunction "1_1") (pintype "unspecified"))
    )
    (net (code "68") (name "Net-(LED4-K)") (class "Default")
      (node (ref "LED4") (pin "2") (pinfunction "K_2") (pintype "unspecified"))
      (node (ref "R7") (pin "1") (pinfunction "1_1") (pintype "unspecified"))
    )
    (net (code "69") (name "Net-(LED5-K)") (class "Default")
      (node (ref "LED5") (pin "2") (pinfunction "K_2") (pintype "unspecified"))
      (node (ref "R8") (pin "1") (pinfunction "1_1") (pintype "unspecified"))
    )
    (net (code "70") (name "Net-(LED6-K)") (class "Default")
      (node (ref "LED6") (pin "2") (pinfunction "K_2") (pintype "unspecified"))
      (node (ref "R9") (pin "1") (pinfunction "1_1") (pintype "unspecified"))
    )
    (net (code "71") (name "Net-(LED7-K)") (class "Default")
      (node (ref "LED7") (pin "2") (pinfunction "K_2") (pintype "unspecified"))
      (node (ref "R10") (pin "1") (pinfunction "1_1") (pintype "unspecified"))
    )
    (net (code "72") (name "Net-(LED8-K)") (class "Default")
      (node (ref "LED8") (pin "2") (pinfunction "K_2") (pintype "unspecified"))
      (node (ref "R11") (pin "1") (pinfunction "1_1") (pintype "unspecified"))
    )
    (net (code "73") (name "Net-(LED9-K)") (class "Default")
      (node (ref "LED9") (pin "2") (pinfunction "K_2") (pintype "unspecified"))
      (node (ref "R12") (pin "1") (pinfunction "1_1") (pintype "unspecified"))
    )
    (net (code "74") (name "Net-(LED10-A)") (class "Default")
      (node (ref "H14") (pin "1") (pinfunction "1_1") (pintype "unspecified"))
      (node (ref "LED10") (pin "1") (pinfunction "A_1") (pintype "unspecified"))
    )
    (net (code "75") (name "Net-(LED10-K)") (class "Default")
      (node (ref "LED10") (pin "2") (pinfunction "K_2") (pintype "unspecified"))
      (node (ref "R19") (pin "1") (pinfunction "1_1") (pintype "unspecified"))
    )
    (net (code "76") (name "Net-(LED11-A)") (class "Default")
      (node (ref "H14") (pin "2") (pinfunction "2_2") (pintype "unspecified"))
      (node (ref "LED11") (pin "1") (pinfunction "A_1") (pintype "unspecified"))
    )
    (net (code "77") (name "Net-(LED11-K)") (class "Default")
      (node (ref "LED11") (pin "2") (pinfunction "K_2") (pintype "unspecified"))
      (node (ref "R20") (pin "1") (pinfunction "1_1") (pintype "unspecified"))
    )
    (net (code "78") (name "Net-(LED12-A)") (class "Default")
      (node (ref "H14") (pin "3") (pinfunction "3_3") (pintype "unspecified"))
      (node (ref "LED12") (pin "1") (pinfunction "A_1") (pintype "unspecified"))
    )
    (net (code "79") (name "Net-(LED12-K)") (class "Default")
      (node (ref "LED12") (pin "2") (pinfunction "K_2") (pintype "unspecified"))
      (node (ref "R21") (pin "1") (pinfunction "1_1") (pintype "unspecified"))
    )
    (net (code "80") (name "Net-(LED13-A)") (class "Default")
      (node (ref "H14") (pin "4") (pinfunction "4_4") (pintype "unspecified"))
      (node (ref "LED13") (pin "1") (pinfunction "A_1") (pintype "unspecified"))
    )
    (net (code "81") (name "Net-(LED13-K)") (class "Default")
      (node (ref "LED13") (pin "2") (pinfunction "K_2") (pintype "unspecified"))
      (node (ref "R22") (pin "1") (pinfunction "1_1") (pintype "unspecified"))
    )
    (net (code "82") (name "Net-(Q1-B)") (class "Default")
      (node (ref "Q1") (pin "2") (pinfunction "B_2") (pintype "input"))
      (node (ref "R13") (pin "2") (pinfunction "2_2") (pintype "unspecified"))
      (node (ref "R17") (pin "1") (pinfunction "1_1") (pintype "unspecified"))
    )
    (net (code "83") (name "Net-(Q1-C)") (class "Default")
      (node (ref "C3") (pin "2") (pinfunction "2_2") (pintype "unspecified"))
      (node (ref "D1") (pin "2") (pinfunction "2_2") (pintype "unspecified"))
      (node (ref "D3") (pin "1") (pinfunction "1_1") (pintype "unspecified"))
      (node (ref "H28") (pin "1") (pinfunction "1_1") (pintype "unspecified"))
      (node (ref "Q1") (pin "1") (pinfunction "C_1") (pintype "input"))
      (node (ref "Q3") (pin "3") (pinfunction "C_3") (pintype "unspecified"))
    )
    (net (code "84") (name "Net-(Q1-E)") (class "Default")
      (node (ref "D1") (pin "1") (pinfunction "1_1") (pintype "unspecified"))
      (node (ref "D2") (pin "1") (pinfunction "1_1") (pintype "unspecified"))
      (node (ref "H12") (pin "3") (pinfunction "3_3") (pintype "unspecified"))
      (node (ref "H12") (pin "4") (pinfunction "4_4") (pintype "unspecified"))
      (node (ref "H28") (pin "4") (pinfunction "4_4") (pintype "unspecified"))
      (node (ref "Q1") (pin "3") (pinfunction "E_3") (pintype "input"))
      (node (ref "Q2") (pin "3") (pinfunction "E_3") (pintype "input"))
      (node (ref "R17") (pin "2") (pinfunction "2_2") (pintype "unspecified"))
      (node (ref "R18") (pin "1") (pinfunction "1_1") (pintype "unspecified"))
    )
    (net (code "85") (name "Net-(Q2-B)") (class "Default")
      (node (ref "Q2") (pin "2") (pinfunction "B_2") (pintype "input"))
      (node (ref "R14") (pin "1") (pinfunction "1_1") (pintype "unspecified"))
      (node (ref "R18") (pin "2") (pinfunction "2_2") (pintype "unspecified"))
    )
    (net (code "86") (name "Net-(Q2-C)") (class "Default")
      (node (ref "C3") (pin "1") (pinfunction "1_1") (pintype "unspecified"))
      (node (ref "D2") (pin "2") (pinfunction "2_2") (pintype "unspecified"))
      (node (ref "D4") (pin "1") (pinfunction "1_1") (pintype "unspecified"))
      (node (ref "H28") (pin "2") (pinfunction "2_2") (pintype "unspecified"))
      (node (ref "Q2") (pin "1") (pinfunction "C_1") (pintype "input"))
      (node (ref "Q4") (pin "3") (pinfunction "C_3") (pintype "unspecified"))
    )
    (net (code "87") (name "Net-(Q3-B)") (class "Default")
      (node (ref "Q3") (pin "2") (pinfunction "B_2") (pintype "unspecified"))
      (node (ref "R15") (pin "2") (pinfunction "2_2") (pintype "unspecified"))
    )
    (net (code "88") (name "Net-(Q3-E)") (class "Default")
      (node (ref "D3") (pin "2") (pinfunction "2_2") (pintype "unspecified"))
      (node (ref "D4") (pin "2") (pinfunction "2_2") (pintype "unspecified"))
      (node (ref "H12") (pin "1") (pinfunction "1_1") (pintype "unspecified"))
      (node (ref "H12") (pin "2") (pinfunction "2_2") (pintype "unspecified"))
      (node (ref "H28") (pin "3") (pinfunction "3_3") (pintype "unspecified"))
      (node (ref "Q3") (pin "1") (pinfunction "E_1") (pintype "unspecified"))
      (node (ref "Q4") (pin "1") (pinfunction "E_1") (pintype "unspecified"))
    )
    (net (code "89") (name "Net-(Q4-B)") (class "Default")
      (node (ref "Q4") (pin "2") (pinfunction "B_2") (pintype "unspecified"))
      (node (ref "R16") (pin "1") (pinfunction "1_1") (pintype "unspecified"))
    )
    (net (code "90") (name "Net-(U2-A)") (class "Default")
      (node (ref "H26") (pin "1") (pinfunction "1_1") (pintype "unspecified"))
      (node (ref "U2") (pin "11") (pinfunction "A_11") (pintype "unspecified"))
    )
    (net (code "91") (name "Net-(U2-B)") (class "Default")
      (node (ref "H26") (pin "2") (pinfunction "2_2") (pintype "unspecified"))
      (node (ref "U2") (pin "7") (pinfunction "B_7") (pintype "unspecified"))
    )
    (net (code "92") (name "Net-(U2-C)") (class "Default")
      (node (ref "H26") (pin "3") (pinfunction "3_3") (pintype "unspecified"))
      (node (ref "U2") (pin "4") (pinfunction "C_4") (pintype "unspecified"))
    )
    (net (code "93") (name "Net-(U2-COM1)") (class "Default")
      (node (ref "R2") (pin "1") (pinfunction "1_1") (pintype "unspecified"))
      (node (ref "U2") (pin "12") (pinfunction "COM1_12") (pintype "unspecified"))
    )
    (net (code "94") (name "Net-(U2-COM2)") (class "Default")
      (node (ref "R3") (pin "1") (pinfunction "1_1") (pintype "unspecified"))
      (node (ref "U2") (pin "9") (pinfunction "COM2_9") (pintype "unspecified"))
    )
    (net (code "95") (name "Net-(U2-COM3)") (class "Default")
      (node (ref "R4") (pin "1") (pinfunction "1_1") (pintype "unspecified"))
      (node (ref "U2") (pin "8") (pinfunction "COM3_8") (pintype "unspecified"))
    )
    (net (code "96") (name "Net-(U2-COM4)") (class "Default")
      (node (ref "R5") (pin "1") (pinfunction "1_1") (pintype "unspecified"))
      (node (ref "U2") (pin "6") (pinfunction "COM4_6") (pintype "unspecified"))
    )
    (net (code "97") (name "Net-(U2-D)") (class "Default")
      (node (ref "H26") (pin "4") (pinfunction "4_4") (pintype "unspecified"))
      (node (ref "U2") (pin "2") (pinfunction "D_2") (pintype "unspecified"))
    )
    (net (code "98") (name "Net-(U2-DP)") (class "Default")
      (node (ref "H26") (pin "8") (pinfunction "8_8") (pintype "unspecified"))
      (node (ref "U2") (pin "3") (pinfunction "DP_3") (pintype "unspecified"))
    )
    (net (code "99") (name "Net-(U2-E)") (class "Default")
      (node (ref "H26") (pin "5") (pinfunction "5_5") (pintype "unspecified"))
      (node (ref "U2") (pin "1") (pinfunction "E_1") (pintype "unspecified"))
    )
    (net (code "100") (name "Net-(U2-F)") (class "Default")
      (node (ref "H26") (pin "6") (pinfunction "6_6") (pintype "unspecified"))
      (node (ref "U2") (pin "10") (pinfunction "F_10") (pintype "unspecified"))
    )
    (net (code "101") (name "Net-(U2-G)") (class "Default")
      (node (ref "H26") (pin "7") (pinfunction "7_7") (pintype "unspecified"))
      (node (ref "U2") (pin "5") (pinfunction "G_5") (pintype "unspecified"))
    )
    (net (code "102") (name "Net-(U3-1B)") (class "Default")
      (node (ref "H8") (pin "1") (pinfunction "1_1") (pintype "unspecified"))
      (node (ref "U3") (pin "1") (pinfunction "1B_1") (pintype "unspecified"))
    )
    (net (code "103") (name "Net-(U3-2B)") (class "Default")
      (node (ref "H8") (pin "2") (pinfunction "2_2") (pintype "unspecified"))
      (node (ref "U3") (pin "2") (pinfunction "2B_2") (pintype "unspecified"))
    )
    (net (code "104") (name "Net-(U3-3B)") (class "Default")
      (node (ref "H8") (pin "3") (pinfunction "3_3") (pintype "unspecified"))
      (node (ref "U3") (pin "3") (pinfunction "3B_3") (pintype "unspecified"))
    )
    (net (code "105") (name "Net-(U3-4B)") (class "Default")
      (node (ref "H8") (pin "4") (pinfunction "4_4") (pintype "unspecified"))
      (node (ref "U3") (pin "4") (pinfunction "4B_4") (pintype "unspecified"))
    )
    (net (code "106") (name "Net-(U3-5B)") (class "Default")
      (node (ref "H8") (pin "5") (pinfunction "5_5") (pintype "unspecified"))
      (node (ref "U3") (pin "5") (pinfunction "5B_5") (pintype "unspecified"))
    )
    (net (code "107") (name "Net-(U3-6B)") (class "Default")
      (node (ref "H8") (pin "6") (pinfunction "6_6") (pintype "unspecified"))
      (node (ref "U3") (pin "6") (pinfunction "6B_6") (pintype "unspecified"))
    )
    (net (code "108") (name "Net-(U3-7B)") (class "Default")
      (node (ref "H8") (pin "7") (pinfunction "7_7") (pintype "unspecified"))
      (node (ref "U3") (pin "7") (pinfunction "7B_7") (pintype "unspecified"))
    )
    (net (code "109") (name "Net-(USB1-D+)") (class "Default")
      (node (ref "H11") (pin "3") (pinfunction "3_3") (pintype "input"))
      (node (ref "USB1") (pin "3") (pinfunction "D+_3") (pintype "unspecified"))
    )
    (net (code "110") (name "Net-(USB1-D-)") (class "Default")
      (node (ref "H11") (pin "2") (pinfunction "2_2") (pintype "input"))
      (node (ref "USB1") (pin "2") (pinfunction "D-_2") (pintype "unspecified"))
    )
    (net (code "111") (name "Net-(USB1-HIDING)") (class "Default")
      (node (ref "H11") (pin "4") (pinfunction "4_4") (pintype "input"))
      (node (ref "USB1") (pin "4") (pinfunction "HIDING_4") (pintype "unspecified"))
    )
    (net (code "112") (name "Net-(USB1-VBUS)") (class "Default")
      (node (ref "H11") (pin "1") (pinfunction "1_1") (pintype "input"))
      (node (ref "USB1") (pin "1") (pinfunction "VBUS_1") (pintype "unspecified"))
    )
    (net (code "113") (name "unconnected-(H5-Pad3)") (class "Default")
      (node (ref "H5") (pin "3") (pinfunction "3_3") (pintype "input+no_connect"))
    )
    (net (code "114") (name "unconnected-(H5-Pad4)") (class "Default")
      (node (ref "H5") (pin "4") (pinfunction "4_4") (pintype "input+no_connect"))
    )
    (net (code "115") (name "unconnected-(H5-Pad6)") (class "Default")
      (node (ref "H5") (pin "6") (pinfunction "6_6") (pintype "input+no_connect"))
    )
    (net (code "116") (name "unconnected-(H5-Pad8)") (class "Default")
      (node (ref "H5") (pin "8") (pinfunction "8_8") (pintype "input+no_connect"))
    )
    (net (code "117") (name "unconnected-(USB1-EP-Pad6)") (class "Default")
      (node (ref "USB1") (pin "6") (pinfunction "EP_6") (pintype "unspecified"))
    )
    (net (code "118") (name "unconnected-(USB1-EP-Pad7)") (class "Default")
      (node (ref "USB1") (pin "7") (pinfunction "EP_7") (pintype "unspecified"))
    )
  )
)
